# MCU.net
KiCad netlist of a schematic drawn in Altium Designer
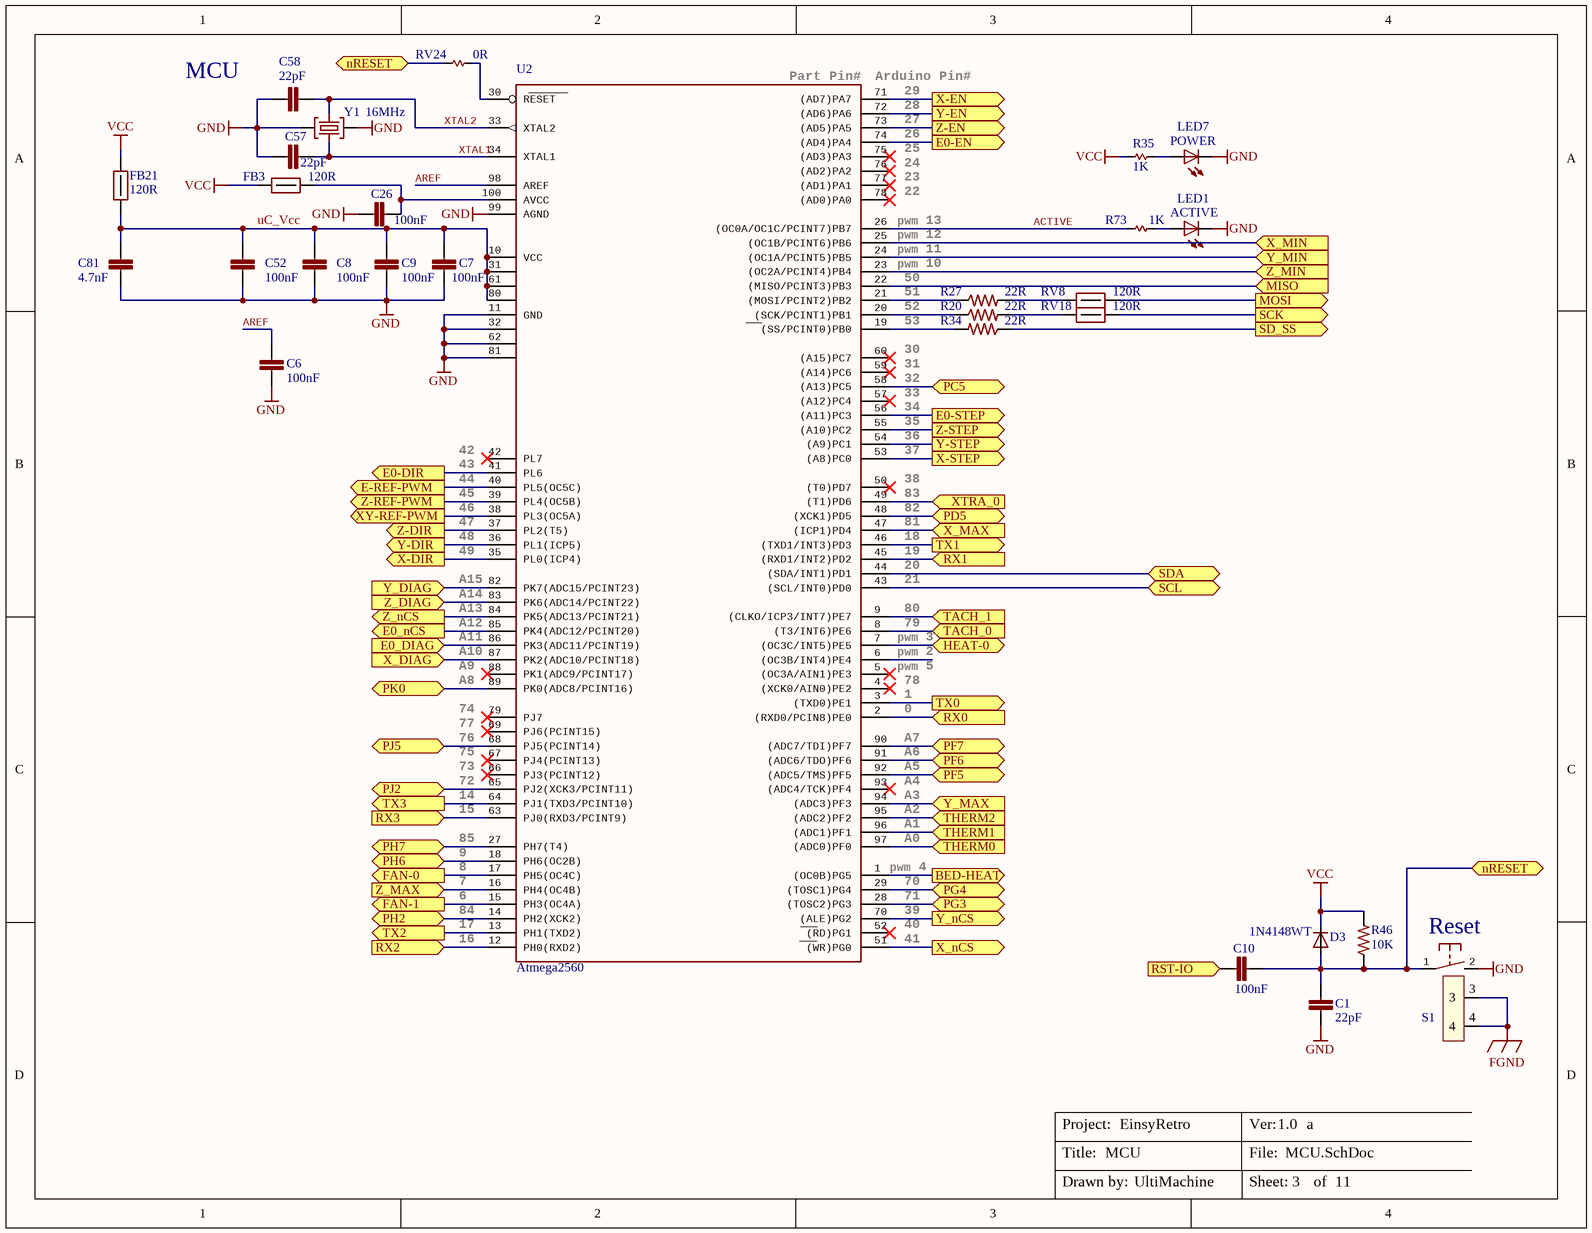
[diagram p0: MCU.SchDoc]

(export (version "E")
  (design (tool "Eeschema 10.0.6"))
  (components
    (comp (ref "C1")
      (value "22pF")
      (footprint "C0402")
      (description "CAP CER 0402 22pF 50V 5% C0G")
      (fields (field (name "MANUFACTURER") "AVX") (field (name "PART") "22pF 50V"))
      (libsource (lib "") (part "04025A220JAT2A_1"))
    )
    (comp (ref "C6")
      (value "100nF")
      (footprint "C0402")
      (description "CAP CER 0402 100nF 16V 10% X7R")
      (fields (field (name "MANUFACTURER") "Murata") (field (name "TOLERANCE") "+/- 10%"))
      (libsource (lib "") (part "GRM155R71C104KA88D_1"))
    )
    (comp (ref "C7")
      (value "100nF")
      (footprint "C0402")
      (description "CAP CER 0402 100nF 16V 10% X7R")
      (fields (field (name "MANUFACTURER") "Murata") (field (name "TOLERANCE") "+/- 10%"))
      (libsource (lib "") (part "GRM155R71C104KA88D_1"))
    )
    (comp (ref "C8")
      (value "100nF")
      (footprint "C0402")
      (description "CAP CER 0402 100nF 16V 10% X7R")
      (fields (field (name "MANUFACTURER") "Murata") (field (name "TOLERANCE") "+/- 10%"))
      (libsource (lib "") (part "GRM155R71C104KA88D_1"))
    )
    (comp (ref "C9")
      (value "100nF")
      (footprint "C0402")
      (description "CAP CER 0402 100nF 16V 10% X7R")
      (fields (field (name "MANUFACTURER") "Murata") (field (name "TOLERANCE") "+/- 10%"))
      (libsource (lib "") (part "GRM155R71C104KA88D_1"))
    )
    (comp (ref "C10")
      (value "100nF")
      (footprint "C0402")
      (description "CAP CER 0402 100nF 16V 10% X7R")
      (fields (field (name "MANUFACTURER") "Murata") (field (name "TOLERANCE") "+/- 10%"))
      (libsource (lib "3Delight") (part "GRM155R71C104KA88D"))
    )
    (comp (ref "C26")
      (value "100nF")
      (footprint "C0402")
      (description "CAP CER 0402 100nF 16V 10% X7R")
      (fields (field (name "MANUFACTURER") "Murata") (field (name "TOLERANCE") "+/- 10%"))
      (libsource (lib "") (part "GRM155R71C104KA88D_2"))
    )
    (comp (ref "C52")
      (value "100nF")
      (footprint "C0402")
      (description "CAP CER 0402 100nF 16V 10% X7R")
      (fields (field (name "MANUFACTURER") "Murata") (field (name "TOLERANCE") "+/- 10%"))
      (libsource (lib "") (part "GRM155R71C104KA88D_1"))
    )
    (comp (ref "C57")
      (value "22pF")
      (footprint "C0402")
      (description "CAP CER 0402 22pF 50V 5% C0G")
      (fields (field (name "MANUFACTURER") "AVX") (field (name "PART") "22pF 50V"))
      (libsource (lib "3Delight") (part "04025A220JAT2A"))
    )
    (comp (ref "C58")
      (value "22pF")
      (footprint "C0402")
      (description "CAP CER 0402 22pF 50V 5% C0G")
      (fields (field (name "MANUFACTURER") "AVX") (field (name "PART") "22pF 50V"))
      (libsource (lib "3Delight") (part "04025A220JAT2A"))
    )
    (comp (ref "C81")
      (value "4.7nF")
      (footprint "C0402")
      (description "CAP CER 0402 4.7nF 25V 10% X7R")
      (fields (field (name "MANUFACTURER") "YAGEO") (field (name "TOLERANCE") "+/- 10%"))
      (libsource (lib "3Delight") (part "CC0402KRX7R8BB472"))
    )
    (comp (ref "D3")
      (value "1N4148WT")
      (footprint "SOD523")
      (description "DIODE SOD523")
      (fields (field (name "MANUFACTURER") "Fairchild") (field (name "TOLERANCE") "NA"))
      (libsource (lib "3Delight") (part "1N4148WT"))
    )
    (comp (ref "FB3")
      (value "120R")
      (footprint "FB0603")
      (description "FERRITE BEAD 120 OHM 0603 1LN")
      (fields (field (name "MANUFACTURER") "Samsung") (field (name "PART") "FERRITE 120R 3A 0603"))
      (libsource (lib "3Delight") (part "FERRITE 220R 2.5A 0603"))
    )
    (comp (ref "FB21")
      (value "120R")
      (footprint "FB0603")
      (description "FERRITE BEAD 120 OHM 0603 1LN")
      (fields (field (name "MANUFACTURER") "Samsung") (field (name "PART") "FERRITE 120R 3A 0603"))
      (libsource (lib "Inductors") (part "FERRITE 120R 3A 0603"))
    )
    (comp (ref "LED1")
      (value "YEL")
      (footprint "LED2012120")
      (description "LED 0805 Yellow")
      (fields (field (name "MANUFACTURER") "Dialight") (field (name "TOLERANCE") "NA"))
      (libsource (lib "3Delight") (part "5988140107F"))
    )
    (comp (ref "LED7")
      (value "GRN")
      (footprint "LED2012120")
      (description "LED 0805 Green")
      (fields (field (name "MANUFACTURER") "Dialight") (field (name "TOLERANCE") "NA"))
      (libsource (lib "3Delight") (part "5988170107F"))
    )
    (comp (ref "R20")
      (value "22R")
      (footprint "R0402")
      (description "RES 0402 22r 62.5mW 1%")
      (fields (field (name "MANUFACTURER") "Yageo") (field (name "TOLERANCE") "+/- 1%"))
      (libsource (lib "3Delight") (part "RC0402FR-0722RL"))
    )
    (comp (ref "R27")
      (value "22R")
      (footprint "R0402")
      (description "RES 0402 22r 62.5mW 1%")
      (fields (field (name "MANUFACTURER") "Yageo") (field (name "TOLERANCE") "+/- 1%"))
      (libsource (lib "3Delight") (part "RC0402FR-0722RL"))
    )
    (comp (ref "R34")
      (value "22R")
      (footprint "R0402")
      (description "RES 0402 22r 62.5mW 1%")
      (fields (field (name "MANUFACTURER") "Yageo") (field (name "TOLERANCE") "+/- 1%"))
      (libsource (lib "3Delight") (part "RC0402FR-0722RL"))
    )
    (comp (ref "R35")
      (value "1K")
      (footprint "R0402")
      (description "RES SMD 1K OHM 1% 1/16W 0402")
      (fields (field (name "MANUFACTURER") "Yageo") (field (name "PART") "1k"))
      (libsource (lib "3Delight") (part "RC0402FR-071KL"))
    )
    (comp (ref "R46")
      (value "10K")
      (footprint "R0402")
      (description "RES SMD 10K OHM 1% 1/16W 0402")
      (fields (field (name "MANUFACTURER") "Yageo") (field (name "PART") "10k 1% 0402"))
      (libsource (lib "3Delight") (part "RC0402FR-0710KP"))
    )
    (comp (ref "R73")
      (value "1K")
      (footprint "R0402")
      (description "RES SMD 1K OHM 1% 1/16W 0402")
      (fields (field (name "MANUFACTURER") "Yageo") (field (name "PART") "1k"))
      (libsource (lib "3Delight") (part "RC0402FR-071KL"))
    )
    (comp (ref "RV8")
      (value "120R")
      (footprint "R0402")
      (description "FERRITE BEAD 120 OHM 0402 1LN")
      (fields (field (name "MANUFACTURER") "Taiyo Yuden") (field (name "PART") "FERRITE 120R 1A 0402"))
      (libsource (lib "Inductors") (part "FERRITE 120R 1A 0402"))
    )
    (comp (ref "RV18")
      (value "120R")
      (footprint "R0402")
      (description "FERRITE BEAD 120 OHM 0402 1LN")
      (fields (field (name "MANUFACTURER") "Taiyo Yuden") (field (name "PART") "FERRITE 120R 1A 0402"))
      (libsource (lib "Inductors") (part "FERRITE 120R 1A 0402"))
    )
    (comp (ref "RV24")
      (value "0R")
      (footprint "R0402")
      (description "RES SMD 0.0OHM JUMPER 1/10W 0402")
      (fields (field (name "MANUFACTURER") "Panasonic") (field (name "TOLERANCE") "1%"))
      (libsource (lib "Resistors") (part "0R 0402"))
    )
    (comp (ref "S1")
      (value "1571610-2")
      (footprint "B3F-31XX")
      (description "SWTCH Momentary Washable")
      (fields (field (name "MANUFACTURER") "TE") (field (name "PART") "Tact PB R/A"))
      (libsource (lib "3Delight") (part "1571610-2"))
    )
    (comp (ref "U2")
      (value "Atmega2560")
      (footprint "TSQFP50P1600X1600X120-100L")
      (fields
        (field (name "MANUFACTURER") "Microchip")
        (field (name "PART") "ATMEGA2560")
        (field (name "TOLERANCE") "NA")
      )
      (libsource (lib "ICs-uC") (part "ATMEGA2560AU_SM"))
    )
    (comp (ref "Y1")
      (value "16MHz")
      (footprint "CRYS320250")
      (description "Crystal 16mHz 10ppm 10pF")
      (fields (field (name "MANUFACTURER") "TXC") (field (name "TOLERANCE") "10ppm"))
      (libsource (lib "3Delight") (part "7M-16.000MEEQ-T"))
    )
  )
  (nets
    (net (code "1") (name "/ACTIVE") (class "Default")
      (node (ref "R73") (pin "2") (pinfunction "2_2") (pintype "passive"))
      (node (ref "U2") (pin "26") (pinfunction "(OC0A/OC1C/PCINT7)PB7_26") (pintype "passive"))
    )
    (net (code "2") (name "/AREF") (class "Default")
      (node (ref "C6") (pin "1") (pinfunction "1_1") (pintype "passive"))
      (node (ref "U2") (pin "98") (pinfunction "AREF_98") (pintype "passive"))
    )
    (net (code "3") (name "/BED-HEAT") (class "Default")
      (node (ref "U2") (pin "1") (pinfunction "(OC0B)PG5_1") (pintype "passive"))
    )
    (net (code "4") (name "/E-REF-PWM") (class "Default")
      (node (ref "U2") (pin "40") (pinfunction "PL5(OC5C)_40") (pintype "passive"))
    )
    (net (code "5") (name "/E0-DIR") (class "Default")
      (node (ref "U2") (pin "41") (pinfunction "PL6_41") (pintype "passive"))
    )
    (net (code "6") (name "/E0-EN") (class "Default")
      (node (ref "U2") (pin "74") (pinfunction "(AD4)PA4_74") (pintype "passive"))
    )
    (net (code "7") (name "/E0-STEP") (class "Default")
      (node (ref "U2") (pin "56") (pinfunction "(A11)PC3_56") (pintype "passive"))
    )
    (net (code "8") (name "/E0_DIAG") (class "Default")
      (node (ref "U2") (pin "86") (pinfunction "PK3(ADC11/PCINT19)_86") (pintype "passive"))
    )
    (net (code "9") (name "/E0_nCS") (class "Default")
      (node (ref "U2") (pin "85") (pinfunction "PK4(ADC12/PCINT20)_85") (pintype "passive"))
    )
    (net (code "10") (name "/FAN-0") (class "Default")
      (node (ref "U2") (pin "17") (pinfunction "PH5(OC4C)_17") (pintype "passive"))
    )
    (net (code "11") (name "/FAN-1") (class "Default")
      (node (ref "U2") (pin "15") (pinfunction "PH3(OC4A)_15") (pintype "passive"))
    )
    (net (code "12") (name "/HEAT-0") (class "Default")
      (node (ref "U2") (pin "7") (pinfunction "(OC3C/INT5)PE5_7") (pintype "passive"))
    )
    (net (code "13") (name "/MISO") (class "Default")
      (node (ref "U2") (pin "22") (pinfunction "(MISO/PCINT3)PB3_22") (pintype "passive"))
    )
    (net (code "14") (name "/MOSI") (class "Default")
      (node (ref "RV8") (pin "2") (pinfunction "2_2") (pintype "passive"))
    )
    (net (code "15") (name "/PC5") (class "Default")
      (node (ref "U2") (pin "58") (pinfunction "(A13)PC5_58") (pintype "passive"))
    )
    (net (code "16") (name "/PD5") (class "Default")
      (node (ref "U2") (pin "48") (pinfunction "(XCK1)PD5_48") (pintype "passive"))
    )
    (net (code "17") (name "/PF5") (class "Default")
      (node (ref "U2") (pin "92") (pinfunction "(ADC5/TMS)PF5_92") (pintype "passive"))
    )
    (net (code "18") (name "/PF6") (class "Default")
      (node (ref "U2") (pin "91") (pinfunction "(ADC6/TDO)PF6_91") (pintype "passive"))
    )
    (net (code "19") (name "/PF7") (class "Default")
      (node (ref "U2") (pin "90") (pinfunction "(ADC7/TDI)PF7_90") (pintype "passive"))
    )
    (net (code "20") (name "/PG3") (class "Default")
      (node (ref "U2") (pin "28") (pinfunction "(TOSC2)PG3_28") (pintype "passive"))
    )
    (net (code "21") (name "/PG4") (class "Default")
      (node (ref "U2") (pin "29") (pinfunction "(TOSC1)PG4_29") (pintype "passive"))
    )
    (net (code "22") (name "/PH2") (class "Default")
      (node (ref "U2") (pin "14") (pinfunction "PH2(XCK2)_14") (pintype "passive"))
    )
    (net (code "23") (name "/PH6") (class "Default")
      (node (ref "U2") (pin "18") (pinfunction "PH6(OC2B)_18") (pintype "passive"))
    )
    (net (code "24") (name "/PH7") (class "Default")
      (node (ref "U2") (pin "27") (pinfunction "PH7(T4)_27") (pintype "passive"))
    )
    (net (code "25") (name "/PJ2") (class "Default")
      (node (ref "U2") (pin "65") (pinfunction "PJ2(XCK3/PCINT11)_65") (pintype "passive"))
    )
    (net (code "26") (name "/PJ5") (class "Default")
      (node (ref "U2") (pin "68") (pinfunction "PJ5(PCINT14)_68") (pintype "passive"))
    )
    (net (code "27") (name "/PK0") (class "Default")
      (node (ref "U2") (pin "89") (pinfunction "PK0(ADC8/PCINT16)_89") (pintype "passive"))
    )
    (net (code "28") (name "/RST-IO") (class "Default")
      (node (ref "C10") (pin "1") (pinfunction "1_1") (pintype "passive"))
    )
    (net (code "29") (name "/RX0") (class "Default")
      (node (ref "U2") (pin "2") (pinfunction "(RXD0/PCIN8)PE0_2") (pintype "passive"))
    )
    (net (code "30") (name "/RX1") (class "Default")
      (node (ref "U2") (pin "45") (pinfunction "(RXD1/INT2)PD2_45") (pintype "passive"))
    )
    (net (code "31") (name "/RX2") (class "Default")
      (node (ref "U2") (pin "12") (pinfunction "PH0(RXD2)_12") (pintype "passive"))
    )
    (net (code "32") (name "/RX3") (class "Default")
      (node (ref "U2") (pin "63") (pinfunction "PJ0(RXD3/PCINT9)_63") (pintype "passive"))
    )
    (net (code "33") (name "/SCK") (class "Default")
      (node (ref "RV18") (pin "2") (pinfunction "2_2") (pintype "passive"))
    )
    (net (code "34") (name "/SCL") (class "Default")
      (node (ref "U2") (pin "43") (pinfunction "(SCL/INT0)PD0_43") (pintype "passive"))
    )
    (net (code "35") (name "/SDA") (class "Default")
      (node (ref "U2") (pin "44") (pinfunction "(SDA/INT1)PD1_44") (pintype "passive"))
    )
    (net (code "36") (name "/SD_SS") (class "Default")
      (node (ref "R34") (pin "1") (pinfunction "1_1") (pintype "passive"))
    )
    (net (code "37") (name "/TACH_0") (class "Default")
      (node (ref "U2") (pin "8") (pinfunction "(T3/INT6)PE6_8") (pintype "passive"))
    )
    (net (code "38") (name "/TACH_1") (class "Default")
      (node (ref "U2") (pin "9") (pinfunction "(CLKO/ICP3/INT7)PE7_9") (pintype "passive"))
    )
    (net (code "39") (name "/THERM0") (class "Default")
      (node (ref "U2") (pin "97") (pinfunction "(ADC0)PF0_97") (pintype "passive"))
    )
    (net (code "40") (name "/THERM1") (class "Default")
      (node (ref "U2") (pin "96") (pinfunction "(ADC1)PF1_96") (pintype "passive"))
    )
    (net (code "41") (name "/THERM2") (class "Default")
      (node (ref "U2") (pin "95") (pinfunction "(ADC2)PF2_95") (pintype "passive"))
    )
    (net (code "42") (name "/TX0") (class "Default")
      (node (ref "U2") (pin "3") (pinfunction "(TXD0)PE1_3") (pintype "passive"))
    )
    (net (code "43") (name "/TX1") (class "Default")
      (node (ref "U2") (pin "46") (pinfunction "(TXD1/INT3)PD3_46") (pintype "passive"))
    )
    (net (code "44") (name "/TX2") (class "Default")
      (node (ref "U2") (pin "13") (pinfunction "PH1(TXD2)_13") (pintype "passive"))
    )
    (net (code "45") (name "/TX3") (class "Default")
      (node (ref "U2") (pin "64") (pinfunction "PJ1(TXD3/PCINT10)_64") (pintype "passive"))
    )
    (net (code "46") (name "/X-DIR") (class "Default")
      (node (ref "U2") (pin "35") (pinfunction "PL0(ICP4)_35") (pintype "passive"))
    )
    (net (code "47") (name "/X-EN") (class "Default")
      (node (ref "U2") (pin "71") (pinfunction "(AD7)PA7_71") (pintype "passive"))
    )
    (net (code "48") (name "/X-STEP") (class "Default")
      (node (ref "U2") (pin "53") (pinfunction "(A8)PC0_53") (pintype "passive"))
    )
    (net (code "49") (name "/XTAL1") (class "Default")
      (node (ref "C57") (pin "1") (pinfunction "1_1") (pintype "passive"))
      (node (ref "U2") (pin "34") (pinfunction "XTAL1_34") (pintype "passive"))
      (node (ref "Y1") (pin "1") (pinfunction "C1_1") (pintype "passive"))
    )
    (net (code "50") (name "/XTAL2") (class "Default")
      (node (ref "C58") (pin "1") (pinfunction "1_1") (pintype "passive"))
      (node (ref "U2") (pin "33") (pinfunction "XTAL2_33") (pintype "output"))
      (node (ref "Y1") (pin "3") (pinfunction "C2_3") (pintype "passive"))
    )
    (net (code "51") (name "/XTRA_0") (class "Default")
      (node (ref "U2") (pin "49") (pinfunction "(T1)PD6_49") (pintype "passive"))
    )
    (net (code "52") (name "/XY-REF-PWM") (class "Default")
      (node (ref "U2") (pin "38") (pinfunction "PL3(OC5A)_38") (pintype "passive"))
    )
    (net (code "53") (name "/X_DIAG") (class "Default")
      (node (ref "U2") (pin "87") (pinfunction "PK2(ADC10/PCINT18)_87") (pintype "passive"))
    )
    (net (code "54") (name "/X_MAX") (class "Default")
      (node (ref "U2") (pin "47") (pinfunction "(ICP1)PD4_47") (pintype "passive"))
    )
    (net (code "55") (name "/X_MIN") (class "Default")
      (node (ref "U2") (pin "25") (pinfunction "(OC1B/PCINT6)PB6_25") (pintype "passive"))
    )
    (net (code "56") (name "/X_nCS") (class "Default")
      (node (ref "U2") (pin "51") (pinfunction "(WR)PG0_51") (pintype "passive"))
    )
    (net (code "57") (name "/Y-DIR") (class "Default")
      (node (ref "U2") (pin "36") (pinfunction "PL1(ICP5)_36") (pintype "passive"))
    )
    (net (code "58") (name "/Y-EN") (class "Default")
      (node (ref "U2") (pin "72") (pinfunction "(AD6)PA6_72") (pintype "passive"))
    )
    (net (code "59") (name "/Y-STEP") (class "Default")
      (node (ref "U2") (pin "54") (pinfunction "(A9)PC1_54") (pintype "passive"))
    )
    (net (code "60") (name "/Y_DIAG") (class "Default")
      (node (ref "U2") (pin "82") (pinfunction "PK7(ADC15/PCINT23)_82") (pintype "passive"))
    )
    (net (code "61") (name "/Y_MAX") (class "Default")
      (node (ref "U2") (pin "94") (pinfunction "(ADC3)PF3_94") (pintype "passive"))
    )
    (net (code "62") (name "/Y_MIN") (class "Default")
      (node (ref "U2") (pin "24") (pinfunction "(OC1A/PCINT5)PB5_24") (pintype "passive"))
    )
    (net (code "63") (name "/Y_nCS") (class "Default")
      (node (ref "U2") (pin "70") (pinfunction "(ALE)PG2_70") (pintype "passive"))
    )
    (net (code "64") (name "/Z-DIR") (class "Default")
      (node (ref "U2") (pin "37") (pinfunction "PL2(T5)_37") (pintype "passive"))
    )
    (net (code "65") (name "/Z-EN") (class "Default")
      (node (ref "U2") (pin "73") (pinfunction "(AD5)PA5_73") (pintype "passive"))
    )
    (net (code "66") (name "/Z-REF-PWM") (class "Default")
      (node (ref "U2") (pin "39") (pinfunction "PL4(OC5B)_39") (pintype "passive"))
    )
    (net (code "67") (name "/Z-STEP") (class "Default")
      (node (ref "U2") (pin "55") (pinfunction "(A10)PC2_55") (pintype "passive"))
    )
    (net (code "68") (name "/Z_DIAG") (class "Default")
      (node (ref "U2") (pin "83") (pinfunction "PK6(ADC14/PCINT22)_83") (pintype "passive"))
    )
    (net (code "69") (name "/Z_MAX") (class "Default")
      (node (ref "U2") (pin "16") (pinfunction "PH4(OC4B)_16") (pintype "passive"))
    )
    (net (code "70") (name "/Z_MIN") (class "Default")
      (node (ref "U2") (pin "23") (pinfunction "(OC2A/PCINT4)PB4_23") (pintype "passive"))
    )
    (net (code "71") (name "/Z_nCS") (class "Default")
      (node (ref "U2") (pin "84") (pinfunction "PK5(ADC13/PCINT21)_84") (pintype "passive"))
    )
    (net (code "72") (name "/nRESET") (class "Default")
      (node (ref "C1") (pin "1") (pinfunction "1_1") (pintype "passive"))
      (node (ref "C10") (pin "2") (pinfunction "2_2") (pintype "passive"))
      (node (ref "D3") (pin "A") (pinfunction "A_A") (pintype "passive"))
      (node (ref "R46") (pin "1") (pinfunction "1_1") (pintype "passive"))
      (node (ref "RV24") (pin "1") (pinfunction "1_1") (pintype "passive"))
      (node (ref "S1") (pin "1") (pinfunction "P_1") (pintype "passive"))
    )
    (net (code "73") (name "/uC_Vcc") (class "Default")
      (node (ref "C52") (pin "1") (pinfunction "1_1") (pintype "passive"))
      (node (ref "C7") (pin "1") (pinfunction "1_1") (pintype "passive"))
      (node (ref "C8") (pin "1") (pinfunction "1_1") (pintype "passive"))
      (node (ref "C81") (pin "1") (pinfunction "1_1") (pintype "passive"))
      (node (ref "C9") (pin "1") (pinfunction "1_1") (pintype "passive"))
      (node (ref "FB21") (pin "2") (pinfunction "2_2") (pintype "passive"))
      (node (ref "U2") (pin "10") (pinfunction "VCC_10") (pintype "power_in"))
      (node (ref "U2") (pin "31") (pinfunction "VCC1_31") (pintype "power_in"))
      (node (ref "U2") (pin "61") (pinfunction "VCC2_61") (pintype "power_in"))
      (node (ref "U2") (pin "80") (pinfunction "VCC3_80") (pintype "power_in"))
    )
    (net (code "74") (name "FGND") (class "Default")
      (node (ref "S1") (pin "3") (pinfunction "3_3") (pintype "power_in"))
      (node (ref "S1") (pin "4") (pinfunction "4_4") (pintype "power_in"))
    )
    (net (code "75") (name "GND") (class "Default")
      (node (ref "C1") (pin "2") (pinfunction "2_2") (pintype "passive"))
      (node (ref "C26") (pin "2") (pinfunction "2_2") (pintype "passive"))
      (node (ref "C52") (pin "2") (pinfunction "2_2") (pintype "passive"))
      (node (ref "C57") (pin "2") (pinfunction "2_2") (pintype "passive"))
      (node (ref "C58") (pin "2") (pinfunction "2_2") (pintype "passive"))
      (node (ref "C6") (pin "2") (pinfunction "2_2") (pintype "passive"))
      (node (ref "C7") (pin "2") (pinfunction "2_2") (pintype "passive"))
      (node (ref "C8") (pin "2") (pinfunction "2_2") (pintype "passive"))
      (node (ref "C81") (pin "2") (pinfunction "2_2") (pintype "passive"))
      (node (ref "C9") (pin "2") (pinfunction "2_2") (pintype "passive"))
      (node (ref "LED1") (pin "C") (pinfunction "C_C") (pintype "passive"))
      (node (ref "LED7") (pin "C") (pinfunction "C_C") (pintype "passive"))
      (node (ref "S1") (pin "2") (pinfunction "S_2") (pintype "passive"))
      (node (ref "U2") (pin "11") (pinfunction "GND_11") (pintype "power_in"))
      (node (ref "U2") (pin "32") (pinfunction "GND1_32") (pintype "power_in"))
      (node (ref "U2") (pin "62") (pinfunction "GND2_62") (pintype "power_in"))
      (node (ref "U2") (pin "81") (pinfunction "GND3_81") (pintype "power_in"))
      (node (ref "U2") (pin "99") (pinfunction "AGND_99") (pintype "power_in"))
      (node (ref "Y1") (pin "2") (pinfunction "GND_2") (pintype "passive"))
      (node (ref "Y1") (pin "4") (pinfunction "GND_4") (pintype "passive"))
    )
    (net (code "76") (name "Net-(LED1-PadA)") (class "Default")
      (node (ref "LED1") (pin "A") (pinfunction "A_A") (pintype "passive"))
      (node (ref "R73") (pin "1") (pinfunction "1_1") (pintype "passive"))
    )
    (net (code "77") (name "Net-(LED7-PadA)") (class "Default")
      (node (ref "LED7") (pin "A") (pinfunction "A_A") (pintype "passive"))
      (node (ref "R35") (pin "1") (pinfunction "1_1") (pintype "passive"))
    )
    (net (code "78") (name "Net-(R20-Pad2)") (class "Default")
      (node (ref "R20") (pin "2") (pinfunction "2_2") (pintype "passive"))
      (node (ref "RV18") (pin "1") (pinfunction "1_1") (pintype "passive"))
    )
    (net (code "79") (name "Net-(R27-Pad2)") (class "Default")
      (node (ref "R27") (pin "2") (pinfunction "2_2") (pintype "passive"))
      (node (ref "RV8") (pin "1") (pinfunction "1_1") (pintype "passive"))
    )
    (net (code "80") (name "Net-(U2-(MOSI{slash}PCINT2)PB2)") (class "Default")
      (node (ref "R27") (pin "1") (pinfunction "1_1") (pintype "passive"))
      (node (ref "U2") (pin "21") (pinfunction "(MOSI/PCINT2)PB2_21") (pintype "passive"))
    )
    (net (code "81") (name "Net-(U2-(SCK{slash}PCINT1)PB1)") (class "Default")
      (node (ref "R20") (pin "1") (pinfunction "1_1") (pintype "passive"))
      (node (ref "U2") (pin "20") (pinfunction "(SCK/PCINT1)PB1_20") (pintype "passive"))
    )
    (net (code "82") (name "Net-(U2-(SS{slash}PCINT0)PB0)") (class "Default")
      (node (ref "R34") (pin "2") (pinfunction "2_2") (pintype "passive"))
      (node (ref "U2") (pin "19") (pinfunction "(SS/PCINT0)PB0_19") (pintype "passive"))
    )
    (net (code "83") (name "Net-(U2-AVCC)") (class "Default")
      (node (ref "C26") (pin "1") (pinfunction "1_1") (pintype "passive"))
      (node (ref "FB3") (pin "2") (pinfunction "2_2") (pintype "passive"))
      (node (ref "U2") (pin "100") (pinfunction "AVCC_100") (pintype "power_in"))
    )
    (net (code "84") (name "Net-(U2-RESET)") (class "Default")
      (node (ref "RV24") (pin "2") (pinfunction "2_2") (pintype "passive"))
      (node (ref "U2") (pin "30") (pinfunction "RESET_30") (pintype "passive"))
    )
    (net (code "85") (name "VCC") (class "Default")
      (node (ref "D3") (pin "C") (pinfunction "C_C") (pintype "passive"))
      (node (ref "FB21") (pin "1") (pinfunction "1_1") (pintype "passive"))
      (node (ref "FB3") (pin "1") (pinfunction "1_1") (pintype "passive"))
      (node (ref "R35") (pin "2") (pinfunction "2_2") (pintype "passive"))
      (node (ref "R46") (pin "2") (pinfunction "2_2") (pintype "passive"))
    )
    (net (code "86") (name "unconnected-(U2-(A12)PC4-Pad57)") (class "Default")
      (node (ref "U2") (pin "57") (pinfunction "(A12)PC4_57") (pintype "passive+no_connect"))
    )
    (net (code "87") (name "unconnected-(U2-(A14)PC6-Pad59)") (class "Default")
      (node (ref "U2") (pin "59") (pinfunction "(A14)PC6_59") (pintype "passive+no_connect"))
    )
    (net (code "88") (name "unconnected-(U2-(A15)PC7-Pad60)") (class "Default")
      (node (ref "U2") (pin "60") (pinfunction "(A15)PC7_60") (pintype "passive+no_connect"))
    )
    (net (code "89") (name "unconnected-(U2-(AD0)PA0-Pad78)") (class "Default")
      (node (ref "U2") (pin "78") (pinfunction "(AD0)PA0_78") (pintype "passive+no_connect"))
    )
    (net (code "90") (name "unconnected-(U2-(AD1)PA1-Pad77)") (class "Default")
      (node (ref "U2") (pin "77") (pinfunction "(AD1)PA1_77") (pintype "passive+no_connect"))
    )
    (net (code "91") (name "unconnected-(U2-(AD2)PA2-Pad76)") (class "Default")
      (node (ref "U2") (pin "76") (pinfunction "(AD2)PA2_76") (pintype "passive+no_connect"))
    )
    (net (code "92") (name "unconnected-(U2-(AD3)PA3-Pad75)") (class "Default")
      (node (ref "U2") (pin "75") (pinfunction "(AD3)PA3_75") (pintype "passive+no_connect"))
    )
    (net (code "93") (name "unconnected-(U2-(ADC4{slash}TCK)PF4-Pad93)") (class "Default")
      (node (ref "U2") (pin "93") (pinfunction "(ADC4/TCK)PF4_93") (pintype "passive+no_connect"))
    )
    (net (code "94") (name "unconnected-(U2-(OC3A{slash}AIN1)PE3-Pad5)") (class "Default")
      (node (ref "U2") (pin "5") (pinfunction "(OC3A/AIN1)PE3_5") (pintype "passive+no_connect"))
    )
    (net (code "95") (name "unconnected-(U2-(OC3B{slash}INT4)PE4-Pad6)") (class "Default")
      (node (ref "U2") (pin "6") (pinfunction "(OC3B/INT4)PE4_6") (pintype "passive"))
    )
    (net (code "96") (name "unconnected-(U2-(RD)PG1-Pad52)") (class "Default")
      (node (ref "U2") (pin "52") (pinfunction "(RD)PG1_52") (pintype "passive+no_connect"))
    )
    (net (code "97") (name "unconnected-(U2-(T0)PD7-Pad50)") (class "Default")
      (node (ref "U2") (pin "50") (pinfunction "(T0)PD7_50") (pintype "passive+no_connect"))
    )
    (net (code "98") (name "unconnected-(U2-(XCK0{slash}AIN0)PE2-Pad4)") (class "Default")
      (node (ref "U2") (pin "4") (pinfunction "(XCK0/AIN0)PE2_4") (pintype "passive+no_connect"))
    )
    (net (code "99") (name "unconnected-(U2-PJ3(PCINT12)-Pad66)") (class "Default")
      (node (ref "U2") (pin "66") (pinfunction "PJ3(PCINT12)_66") (pintype "passive+no_connect"))
    )
    (net (code "100") (name "unconnected-(U2-PJ4(PCINT13)-Pad67)") (class "Default")
      (node (ref "U2") (pin "67") (pinfunction "PJ4(PCINT13)_67") (pintype "passive+no_connect"))
    )
    (net (code "101") (name "unconnected-(U2-PJ6(PCINT15)-Pad69)") (class "Default")
      (node (ref "U2") (pin "69") (pinfunction "PJ6(PCINT15)_69") (pintype "passive+no_connect"))
    )
    (net (code "102") (name "unconnected-(U2-PJ7-Pad79)") (class "Default")
      (node (ref "U2") (pin "79") (pinfunction "PJ7_79") (pintype "passive+no_connect"))
    )
    (net (code "103") (name "unconnected-(U2-PK1(ADC9{slash}PCINT17)-Pad88)") (class "Default")
      (node (ref "U2") (pin "88") (pinfunction "PK1(ADC9/PCINT17)_88") (pintype "passive+no_connect"))
    )
    (net (code "104") (name "unconnected-(U2-PL7-Pad42)") (class "Default")
      (node (ref "U2") (pin "42") (pinfunction "PL7_42") (pintype "passive+no_connect"))
    )
  )
)
